# STM32.net
KiCad netlist of a schematic drawn in Altium Designer
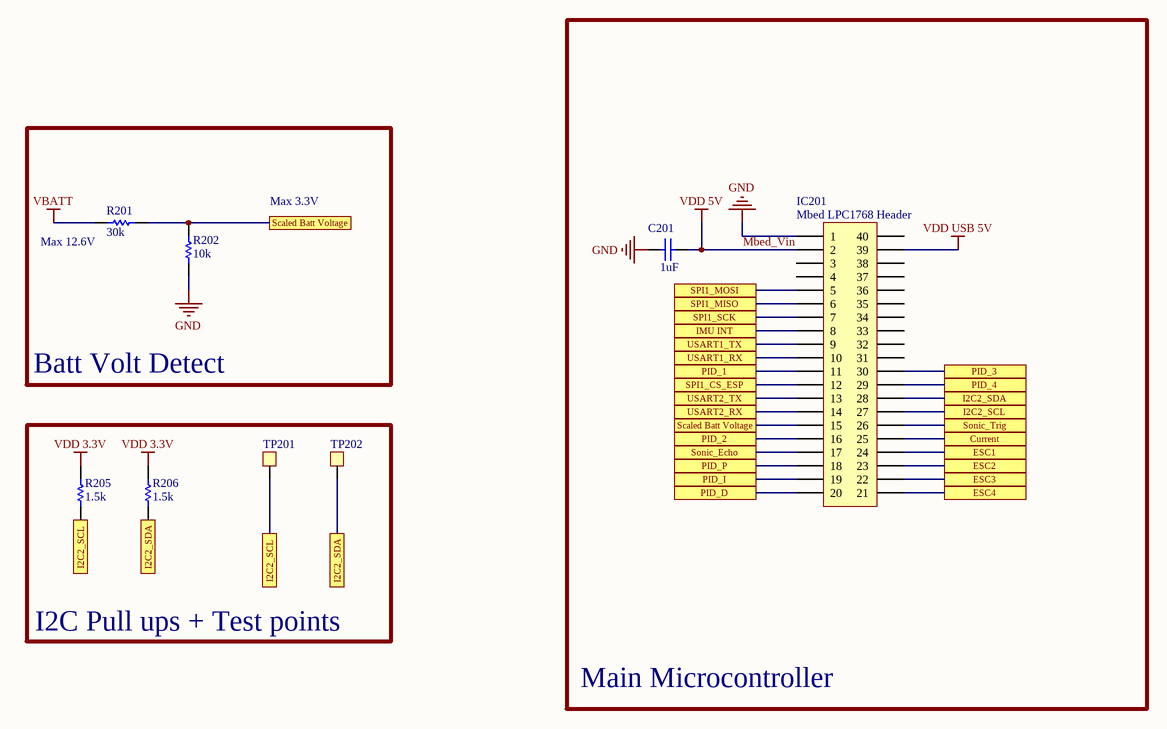
[diagram p0: STM32.SchDoc]

(export (version "E")
  (design (tool "Eeschema 10.0.6"))
  (components
    (comp (ref "C201")
      (value "1uF")
      (footprint "0805 Cap")
      (description "Capacitor Box")
      (fields (field (name "Comment") "0805") (field (name "PUBLISHER") "Altium Limited"))
      (libsource (lib "Miscellaneous Devices") (part "Cap"))
    )
    (comp (ref "IC201")
      (value "Mbed LPC1768 Header")
      (footprint "Mbed LPC1768")
      (fields (field (name "PUBLISHER") "Altium Limited"))
      (libsource (lib "Miscellaneous Connectors") (part "Header 20X2"))
    )
    (comp (ref "R201")
      (value "30k")
      (footprint "0603")
      (description "Resistor")
      (fields (field (name "Comment") "0603") (field (name "PUBLISHER") "Altium Limited"))
      (libsource (lib "Miscellaneous Devices") (part "Res1"))
    )
    (comp (ref "R202")
      (value "10k")
      (footprint "0603")
      (description "Resistor")
      (fields (field (name "Comment") "0603") (field (name "PUBLISHER") "Altium Limited"))
      (libsource (lib "Miscellaneous Devices") (part "Res1"))
    )
    (comp (ref "R205")
      (value "1.5k")
      (footprint "0603")
      (description "Resistor")
      (fields (field (name "Comment") "0603") (field (name "PUBLISHER") "Altium Limited"))
      (libsource (lib "Miscellaneous Devices") (part "Res1"))
    )
    (comp (ref "R206")
      (value "1.5k")
      (footprint "0603")
      (description "Resistor")
      (fields (field (name "Comment") "0603") (field (name "PUBLISHER") "Altium Limited"))
      (libsource (lib "Miscellaneous Devices") (part "Res1"))
    )
    (comp (ref "TP201")
      (value "Test Point")
      (footprint "Test Point THT 1mm")
      (libsource (lib "FYP_Drone") (part "Test Point"))
    )
    (comp (ref "TP202")
      (value "Test Point")
      (footprint "Test Point THT 1mm")
      (libsource (lib "FYP_Drone") (part "Test Point"))
    )
  )
  (nets
    (net (code "1") (name "/Current") (class "Default")
      (node (ref "IC201") (pin "25") (pinfunction "25_25") (pintype "passive"))
    )
    (net (code "2") (name "/ESC1") (class "Default")
      (node (ref "IC201") (pin "24") (pinfunction "24_24") (pintype "passive"))
    )
    (net (code "3") (name "/ESC2") (class "Default")
      (node (ref "IC201") (pin "23") (pinfunction "23_23") (pintype "passive"))
    )
    (net (code "4") (name "/ESC3") (class "Default")
      (node (ref "IC201") (pin "22") (pinfunction "22_22") (pintype "passive"))
    )
    (net (code "5") (name "/ESC4") (class "Default")
      (node (ref "IC201") (pin "21") (pinfunction "21_21") (pintype "passive"))
    )
    (net (code "6") (name "/I2C2_SCL") (class "Default")
      (node (ref "IC201") (pin "27") (pinfunction "27_27") (pintype "passive"))
      (node (ref "R205") (pin "2") (pinfunction "2_2") (pintype "passive"))
      (node (ref "TP201") (pin "1") (pintype "passive"))
    )
    (net (code "7") (name "/I2C2_SDA") (class "Default")
      (node (ref "IC201") (pin "28") (pinfunction "28_28") (pintype "passive"))
      (node (ref "R206") (pin "2") (pinfunction "2_2") (pintype "passive"))
      (node (ref "TP202") (pin "1") (pintype "passive"))
    )
    (net (code "8") (name "/IMU INT") (class "Default")
      (node (ref "IC201") (pin "8") (pinfunction "8_8") (pintype "passive"))
    )
    (net (code "9") (name "/PID_1") (class "Default")
      (node (ref "IC201") (pin "11") (pinfunction "11_11") (pintype "passive"))
    )
    (net (code "10") (name "/PID_2") (class "Default")
      (node (ref "IC201") (pin "16") (pinfunction "16_16") (pintype "passive"))
    )
    (net (code "11") (name "/PID_3") (class "Default")
      (node (ref "IC201") (pin "30") (pinfunction "30_30") (pintype "passive"))
    )
    (net (code "12") (name "/PID_4") (class "Default")
      (node (ref "IC201") (pin "29") (pinfunction "29_29") (pintype "passive"))
    )
    (net (code "13") (name "/PID_D") (class "Default")
      (node (ref "IC201") (pin "20") (pinfunction "20_20") (pintype "passive"))
    )
    (net (code "14") (name "/PID_I") (class "Default")
      (node (ref "IC201") (pin "19") (pinfunction "19_19") (pintype "passive"))
    )
    (net (code "15") (name "/PID_P") (class "Default")
      (node (ref "IC201") (pin "18") (pinfunction "18_18") (pintype "passive"))
    )
    (net (code "16") (name "/SPI1_CS_ESP") (class "Default")
      (node (ref "IC201") (pin "12") (pinfunction "12_12") (pintype "passive"))
    )
    (net (code "17") (name "/SPI1_MISO") (class "Default")
      (node (ref "IC201") (pin "6") (pinfunction "6_6") (pintype "passive"))
    )
    (net (code "18") (name "/SPI1_MOSI") (class "Default")
      (node (ref "IC201") (pin "5") (pinfunction "5_5") (pintype "passive"))
    )
    (net (code "19") (name "/SPI1_SCK") (class "Default")
      (node (ref "IC201") (pin "7") (pinfunction "7_7") (pintype "passive"))
    )
    (net (code "20") (name "/Scaled Batt Voltage") (class "Default")
      (node (ref "IC201") (pin "15") (pinfunction "15_15") (pintype "passive"))
      (node (ref "R201") (pin "2") (pinfunction "2_2") (pintype "passive"))
      (node (ref "R202") (pin "1") (pinfunction "1_1") (pintype "passive"))
    )
    (net (code "21") (name "/Sonic_Echo") (class "Default")
      (node (ref "IC201") (pin "17") (pinfunction "17_17") (pintype "passive"))
    )
    (net (code "22") (name "/Sonic_Trig") (class "Default")
      (node (ref "IC201") (pin "26") (pinfunction "26_26") (pintype "passive"))
    )
    (net (code "23") (name "/USART1_RX") (class "Default")
      (node (ref "IC201") (pin "10") (pinfunction "10_10") (pintype "passive"))
    )
    (net (code "24") (name "/USART1_TX") (class "Default")
      (node (ref "IC201") (pin "9") (pinfunction "9_9") (pintype "passive"))
    )
    (net (code "25") (name "/USART2_RX") (class "Default")
      (node (ref "IC201") (pin "14") (pinfunction "14_14") (pintype "passive"))
    )
    (net (code "26") (name "/USART2_TX") (class "Default")
      (node (ref "IC201") (pin "13") (pinfunction "13_13") (pintype "passive"))
    )
    (net (code "27") (name "GND") (class "Default")
      (node (ref "C201") (pin "2") (pinfunction "2_2") (pintype "passive"))
      (node (ref "IC201") (pin "1") (pinfunction "1_1") (pintype "passive"))
      (node (ref "R202") (pin "2") (pinfunction "2_2") (pintype "passive"))
    )
    (net (code "28") (name "VBATT") (class "Default")
      (node (ref "R201") (pin "1") (pinfunction "1_1") (pintype "passive"))
    )
    (net (code "29") (name "VDD 3.3V") (class "Default")
      (node (ref "R205") (pin "1") (pinfunction "1_1") (pintype "passive"))
      (node (ref "R206") (pin "1") (pinfunction "1_1") (pintype "passive"))
    )
    (net (code "30") (name "VDD 5V") (class "Default")
      (node (ref "C201") (pin "1") (pinfunction "1_1") (pintype "passive"))
      (node (ref "IC201") (pin "2") (pinfunction "2_2") (pintype "passive"))
    )
    (net (code "31") (name "VDD USB 5V") (class "Default")
      (node (ref "IC201") (pin "39") (pinfunction "39_39") (pintype "passive"))
    )
    (net (code "32") (name "unconnected-(IC201-Pad3)") (class "Default")
      (node (ref "IC201") (pin "3") (pinfunction "3_3") (pintype "passive"))
    )
    (net (code "33") (name "unconnected-(IC201-Pad4)") (class "Default")
      (node (ref "IC201") (pin "4") (pinfunction "4_4") (pintype "passive"))
    )
    (net (code "34") (name "unconnected-(IC201-Pad31)") (class "Default")
      (node (ref "IC201") (pin "31") (pinfunction "31_31") (pintype "passive"))
    )
    (net (code "35") (name "unconnected-(IC201-Pad32)") (class "Default")
      (node (ref "IC201") (pin "32") (pinfunction "32_32") (pintype "passive"))
    )
    (net (code "36") (name "unconnected-(IC201-Pad33)") (class "Default")
      (node (ref "IC201") (pin "33") (pinfunction "33_33") (pintype "passive"))
    )
    (net (code "37") (name "unconnected-(IC201-Pad34)") (class "Default")
      (node (ref "IC201") (pin "34") (pinfunction "34_34") (pintype "passive"))
    )
    (net (code "38") (name "unconnected-(IC201-Pad35)") (class "Default")
      (node (ref "IC201") (pin "35") (pinfunction "35_35") (pintype "passive"))
    )
    (net (code "39") (name "unconnected-(IC201-Pad36)") (class "Default")
      (node (ref "IC201") (pin "36") (pinfunction "36_36") (pintype "passive"))
    )
    (net (code "40") (name "unconnected-(IC201-Pad37)") (class "Default")
      (node (ref "IC201") (pin "37") (pinfunction "37_37") (pintype "passive"))
    )
    (net (code "41") (name "unconnected-(IC201-Pad38)") (class "Default")
      (node (ref "IC201") (pin "38") (pinfunction "38_38") (pintype "passive"))
    )
    (net (code "42") (name "unconnected-(IC201-Pad40)") (class "Default")
      (node (ref "IC201") (pin "40") (pinfunction "40_40") (pintype "passive"))
    )
  )
)
